# ZYNQ_SOC_FPGA.net
KiCad netlist of a schematic drawn in Altium Designer
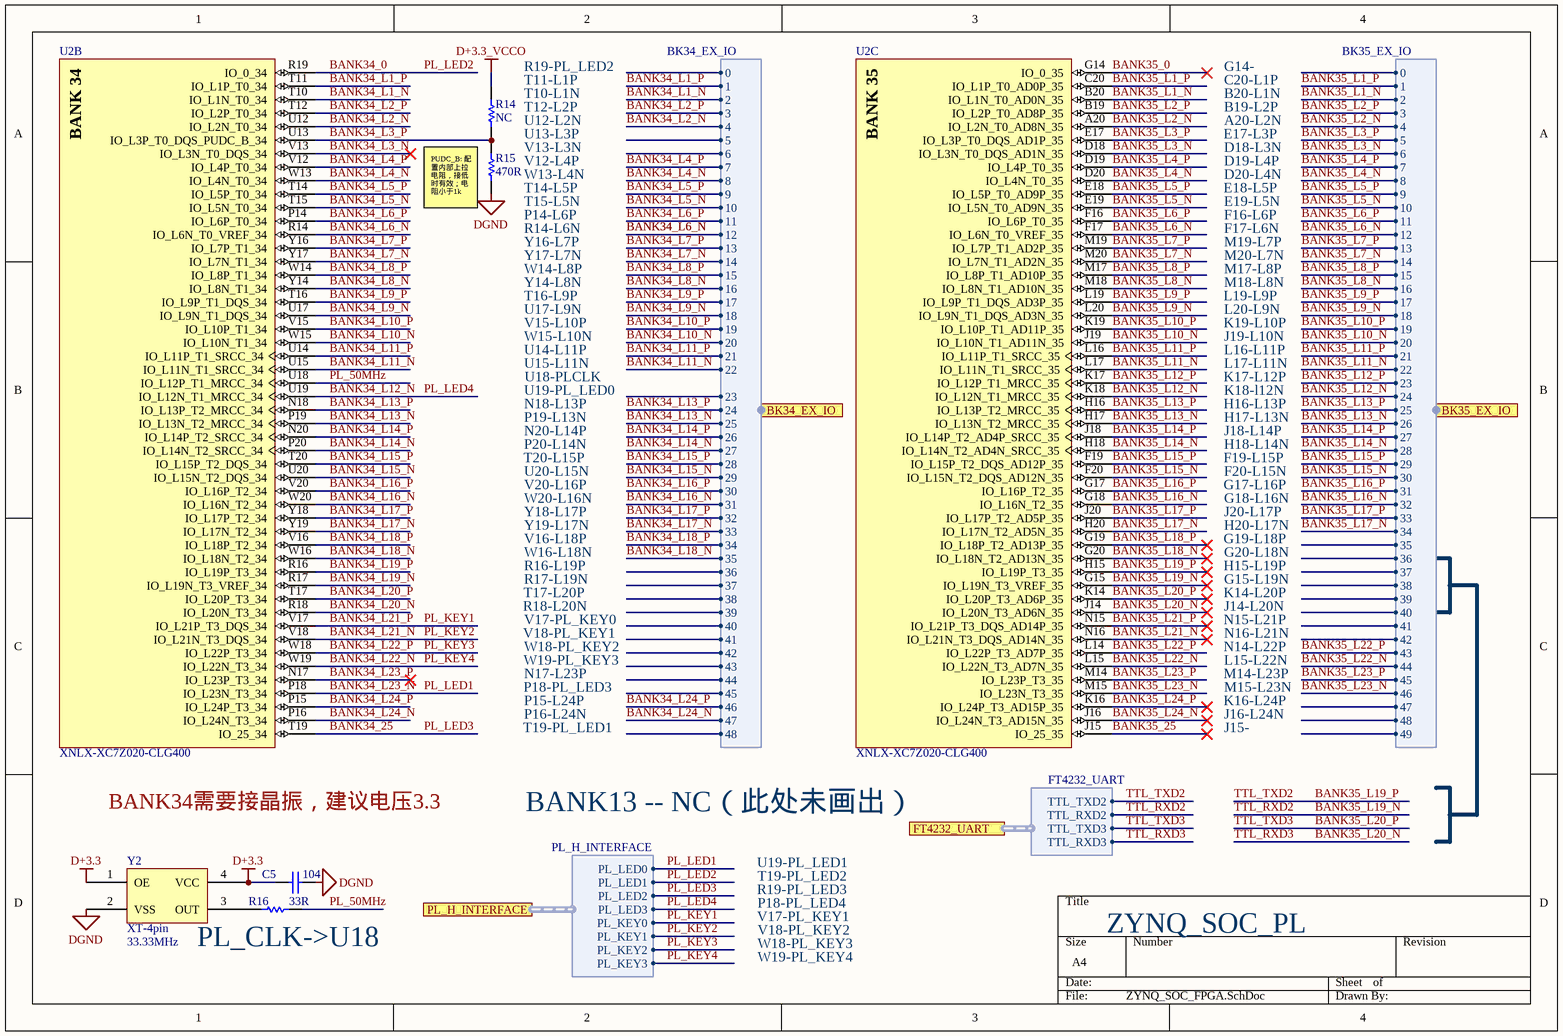
[diagram p0: ZYNQ_SOC_FPGA.SchDoc]

(export (version "E")
  (design (tool "Eeschema 10.0.6"))
  (components
    (comp (ref "C5")
      (value "104")
      (footprint "C 0402_LL")
      (description "Capacitor")
      (fields (field (name "PUBLISHER") "Altium Limited"))
      (libsource (lib "Miscellaneous Devices") (part "Cap"))
    )
    (comp (ref "R14")
      (value "NC")
      (footprint "R 0402_L")
      (description "Resistor")
      (fields (field (name "PUBLISHER") "Altium Limited"))
      (libsource (lib "Miscellaneous Devices") (part "Res1"))
    )
    (comp (ref "R15")
      (value "470R")
      (footprint "R 0402_L")
      (description "Resistor")
      (fields (field (name "PUBLISHER") "Altium Limited"))
      (libsource (lib "Miscellaneous Devices") (part "Res1"))
    )
    (comp (ref "R16")
      (value "33R")
      (footprint "R 0603_L")
      (description "Resistor")
      (fields (field (name "PUBLISHER") "Altium Limited"))
      (libsource (lib "Miscellaneous Devices") (part "Res1"))
    )
    (comp (ref "U2")
      (value "XNLX-XC7Z020-CLG400")
      (footprint "BGA400")
      (description "xilinx双核A9处理器与FPGA集成的SoC")
      (fields (field (name "MANUFACTURER") "xilinx"))
      (libsource (lib "龙井V1") (part "XNLX-XC7Z020-CLG400"))
    )
    (comp (ref "Y2")
      (value "XT-4pin")
      (footprint "5032(P)")
      (description "有源晶振")
      (fields (field (name "MANUFACTURER") "NC") (field (name "ALTIUM_VALUE") "33.33MHz"))
      (libsource (lib "龙井V1") (part "XT-4pin"))
    )
  )
  (nets
    (net (code "5") (name "/BANK34_0") (class "Default")
      (node (ref "U2") (pin "R19") (pinfunction "IO_0_34_R19") (pintype "bidirectional"))
    )
    (net (code "6") (name "/BANK34_25") (class "Default")
      (node (ref "U2") (pin "T19") (pinfunction "IO_25_34_T19") (pintype "bidirectional"))
    )
    (net (code "7") (name "/BANK34_L1_N") (class "Default")
      (node (ref "U2") (pin "T10") (pinfunction "IO_L1N_T0_34_T10") (pintype "bidirectional"))
    )
    (net (code "8") (name "/BANK34_L1_P") (class "Default")
      (node (ref "U2") (pin "T11") (pinfunction "IO_L1P_T0_34_T11") (pintype "bidirectional"))
    )
    (net (code "9") (name "/BANK34_L2_N") (class "Default")
      (node (ref "U2") (pin "U12") (pinfunction "IO_L2N_T0_34_U12") (pintype "bidirectional"))
    )
    (net (code "10") (name "/BANK34_L2_P") (class "Default")
      (node (ref "U2") (pin "T12") (pinfunction "IO_L2P_T0_34_T12") (pintype "bidirectional"))
    )
    (net (code "11") (name "/BANK34_L3_N") (class "Default")
      (node (ref "U2") (pin "V13") (pinfunction "IO_L3N_T0_DQS_34_V13") (pintype "bidirectional+no_connect"))
    )
    (net (code "12") (name "/BANK34_L3_P") (class "Default")
      (node (ref "R14") (pin "1") (pinfunction "1_1") (pintype "passive"))
      (node (ref "R15") (pin "2") (pinfunction "2_2") (pintype "passive"))
      (node (ref "U2") (pin "U13") (pinfunction "IO_L3P_T0_DQS_PUDC_B_34_U13") (pintype "bidirectional"))
    )
    (net (code "13") (name "/BANK34_L4_N") (class "Default")
      (node (ref "U2") (pin "W13") (pinfunction "IO_L4N_T0_34_W13") (pintype "bidirectional"))
    )
    (net (code "14") (name "/BANK34_L4_P") (class "Default")
      (node (ref "U2") (pin "V12") (pinfunction "IO_L4P_T0_34_V12") (pintype "bidirectional"))
    )
    (net (code "15") (name "/BANK34_L5_N") (class "Default")
      (node (ref "U2") (pin "T15") (pinfunction "IO_L5N_T0_34_T15") (pintype "bidirectional"))
    )
    (net (code "16") (name "/BANK34_L5_P") (class "Default")
      (node (ref "U2") (pin "T14") (pinfunction "IO_L5P_T0_34_T14") (pintype "bidirectional"))
    )
    (net (code "17") (name "/BANK34_L6_N") (class "Default")
      (node (ref "U2") (pin "R14") (pinfunction "IO_L6N_T0_VREF_34_R14") (pintype "bidirectional"))
    )
    (net (code "18") (name "/BANK34_L6_P") (class "Default")
      (node (ref "U2") (pin "P14") (pinfunction "IO_L6P_T0_34_P14") (pintype "bidirectional"))
    )
    (net (code "19") (name "/BANK34_L7_N") (class "Default")
      (node (ref "U2") (pin "Y17") (pinfunction "IO_L7N_T1_34_Y17") (pintype "bidirectional"))
    )
    (net (code "20") (name "/BANK34_L7_P") (class "Default")
      (node (ref "U2") (pin "Y16") (pinfunction "IO_L7P_T1_34_Y16") (pintype "bidirectional"))
    )
    (net (code "21") (name "/BANK34_L8_N") (class "Default")
      (node (ref "U2") (pin "Y14") (pinfunction "IO_L8N_T1_34_Y14") (pintype "bidirectional"))
    )
    (net (code "22") (name "/BANK34_L8_P") (class "Default")
      (node (ref "U2") (pin "W14") (pinfunction "IO_L8P_T1_34_W14") (pintype "bidirectional"))
    )
    (net (code "23") (name "/BANK34_L9_N") (class "Default")
      (node (ref "U2") (pin "U17") (pinfunction "IO_L9N_T1_DQS_34_U17") (pintype "bidirectional"))
    )
    (net (code "24") (name "/BANK34_L9_P") (class "Default")
      (node (ref "U2") (pin "T16") (pinfunction "IO_L9P_T1_DQS_34_T16") (pintype "bidirectional"))
    )
    (net (code "25") (name "/BANK34_L10_N") (class "Default")
      (node (ref "U2") (pin "W15") (pinfunction "IO_L10N_T1_34_W15") (pintype "bidirectional"))
    )
    (net (code "26") (name "/BANK34_L10_P") (class "Default")
      (node (ref "U2") (pin "V15") (pinfunction "IO_L10P_T1_34_V15") (pintype "bidirectional"))
    )
    (net (code "27") (name "/BANK34_L11_N") (class "Default")
      (node (ref "U2") (pin "U15") (pinfunction "IO_L11N_T1_SRCC_34_U15") (pintype "bidirectional"))
    )
    (net (code "28") (name "/BANK34_L11_P") (class "Default")
      (node (ref "U2") (pin "U14") (pinfunction "IO_L11P_T1_SRCC_34_U14") (pintype "bidirectional"))
    )
    (net (code "29") (name "/BANK34_L12_N") (class "Default")
      (node (ref "U2") (pin "U19") (pinfunction "IO_L12N_T1_MRCC_34_U19") (pintype "bidirectional"))
    )
    (net (code "30") (name "/BANK34_L13_N") (class "Default")
      (node (ref "U2") (pin "P19") (pinfunction "IO_L13N_T2_MRCC_34_P19") (pintype "bidirectional"))
    )
    (net (code "31") (name "/BANK34_L13_P") (class "Default")
      (node (ref "U2") (pin "N18") (pinfunction "IO_L13P_T2_MRCC_34_N18") (pintype "bidirectional"))
    )
    (net (code "32") (name "/BANK34_L14_N") (class "Default")
      (node (ref "U2") (pin "P20") (pinfunction "IO_L14N_T2_SRCC_34_P20") (pintype "bidirectional"))
    )
    (net (code "33") (name "/BANK34_L14_P") (class "Default")
      (node (ref "U2") (pin "N20") (pinfunction "IO_L14P_T2_SRCC_34_N20") (pintype "bidirectional"))
    )
    (net (code "34") (name "/BANK34_L15_N") (class "Default")
      (node (ref "U2") (pin "U20") (pinfunction "IO_L15N_T2_DQS_34_U20") (pintype "bidirectional"))
    )
    (net (code "35") (name "/BANK34_L15_P") (class "Default")
      (node (ref "U2") (pin "T20") (pinfunction "IO_L15P_T2_DQS_34_T20") (pintype "bidirectional"))
    )
    (net (code "36") (name "/BANK34_L16_N") (class "Default")
      (node (ref "U2") (pin "W20") (pinfunction "IO_L16N_T2_34_W20") (pintype "bidirectional"))
    )
    (net (code "37") (name "/BANK34_L16_P") (class "Default")
      (node (ref "U2") (pin "V20") (pinfunction "IO_L16P_T2_34_V20") (pintype "bidirectional"))
    )
    (net (code "38") (name "/BANK34_L17_N") (class "Default")
      (node (ref "U2") (pin "Y19") (pinfunction "IO_L17N_T2_34_Y19") (pintype "bidirectional"))
    )
    (net (code "39") (name "/BANK34_L17_P") (class "Default")
      (node (ref "U2") (pin "Y18") (pinfunction "IO_L17P_T2_34_Y18") (pintype "bidirectional"))
    )
    (net (code "40") (name "/BANK34_L18_N") (class "Default")
      (node (ref "U2") (pin "W16") (pinfunction "IO_L18N_T2_34_W16") (pintype "bidirectional"))
    )
    (net (code "41") (name "/BANK34_L18_P") (class "Default")
      (node (ref "U2") (pin "V16") (pinfunction "IO_L18P_T2_34_V16") (pintype "bidirectional"))
    )
    (net (code "42") (name "/BANK34_L19_N") (class "Default")
      (node (ref "U2") (pin "R17") (pinfunction "IO_L19N_T3_VREF_34_R17") (pintype "bidirectional"))
    )
    (net (code "43") (name "/BANK34_L19_P") (class "Default")
      (node (ref "U2") (pin "R16") (pinfunction "IO_L19P_T3_34_R16") (pintype "bidirectional"))
    )
    (net (code "44") (name "/BANK34_L20_N") (class "Default")
      (node (ref "U2") (pin "R18") (pinfunction "IO_L20N_T3_34_R18") (pintype "bidirectional"))
    )
    (net (code "45") (name "/BANK34_L20_P") (class "Default")
      (node (ref "U2") (pin "T17") (pinfunction "IO_L20P_T3_34_T17") (pintype "bidirectional"))
    )
    (net (code "46") (name "/BANK34_L21_N") (class "Default")
      (node (ref "U2") (pin "V18") (pinfunction "IO_L21N_T3_DQS_34_V18") (pintype "bidirectional"))
    )
    (net (code "47") (name "/BANK34_L21_P") (class "Default")
      (node (ref "U2") (pin "V17") (pinfunction "IO_L21P_T3_DQS_34_V17") (pintype "bidirectional"))
    )
    (net (code "48") (name "/BANK34_L22_N") (class "Default")
      (node (ref "U2") (pin "W19") (pinfunction "IO_L22N_T3_34_W19") (pintype "bidirectional"))
    )
    (net (code "49") (name "/BANK34_L22_P") (class "Default")
      (node (ref "U2") (pin "W18") (pinfunction "IO_L22P_T3_34_W18") (pintype "bidirectional"))
    )
    (net (code "50") (name "/BANK34_L23_N") (class "Default")
      (node (ref "U2") (pin "P18") (pinfunction "IO_L23N_T3_34_P18") (pintype "bidirectional"))
    )
    (net (code "51") (name "/BANK34_L23_P") (class "Default")
      (node (ref "U2") (pin "N17") (pinfunction "IO_L23P_T3_34_N17") (pintype "bidirectional+no_connect"))
    )
    (net (code "52") (name "/BANK34_L24_N") (class "Default")
      (node (ref "U2") (pin "P16") (pinfunction "IO_L24N_T3_34_P16") (pintype "bidirectional"))
    )
    (net (code "53") (name "/BANK34_L24_P") (class "Default")
      (node (ref "U2") (pin "P15") (pinfunction "IO_L24P_T3_34_P15") (pintype "bidirectional"))
    )
    (net (code "54") (name "/BANK35_0") (class "Default")
      (node (ref "U2") (pin "G14") (pinfunction "IO_0_35_G14") (pintype "bidirectional+no_connect"))
    )
    (net (code "55") (name "/BANK35_25") (class "Default")
      (node (ref "U2") (pin "J15") (pinfunction "IO_25_35_J15") (pintype "bidirectional+no_connect"))
    )
    (net (code "56") (name "/BANK35_L1_N") (class "Default")
      (node (ref "U2") (pin "B20") (pinfunction "IO_L1N_T0_AD0N_35_B20") (pintype "bidirectional"))
    )
    (net (code "57") (name "/BANK35_L1_P") (class "Default")
      (node (ref "U2") (pin "C20") (pinfunction "IO_L1P_T0_AD0P_35_C20") (pintype "bidirectional"))
    )
    (net (code "58") (name "/BANK35_L2_N") (class "Default")
      (node (ref "U2") (pin "A20") (pinfunction "IO_L2N_T0_AD8N_35_A20") (pintype "bidirectional"))
    )
    (net (code "59") (name "/BANK35_L2_P") (class "Default")
      (node (ref "U2") (pin "B19") (pinfunction "IO_L2P_T0_AD8P_35_B19") (pintype "bidirectional"))
    )
    (net (code "60") (name "/BANK35_L3_N") (class "Default")
      (node (ref "U2") (pin "D18") (pinfunction "IO_L3N_T0_DQS_AD1N_35_D18") (pintype "bidirectional"))
    )
    (net (code "61") (name "/BANK35_L3_P") (class "Default")
      (node (ref "U2") (pin "E17") (pinfunction "IO_L3P_T0_DQS_AD1P_35_E17") (pintype "bidirectional"))
    )
    (net (code "62") (name "/BANK35_L4_N") (class "Default")
      (node (ref "U2") (pin "D20") (pinfunction "IO_L4N_T0_35_D20") (pintype "bidirectional"))
    )
    (net (code "63") (name "/BANK35_L4_P") (class "Default")
      (node (ref "U2") (pin "D19") (pinfunction "IO_L4P_T0_35_D19") (pintype "bidirectional"))
    )
    (net (code "64") (name "/BANK35_L5_N") (class "Default")
      (node (ref "U2") (pin "E19") (pinfunction "IO_L5N_T0_AD9N_35_E19") (pintype "bidirectional"))
    )
    (net (code "65") (name "/BANK35_L5_P") (class "Default")
      (node (ref "U2") (pin "E18") (pinfunction "IO_L5P_T0_AD9P_35_E18") (pintype "bidirectional"))
    )
    (net (code "66") (name "/BANK35_L6_N") (class "Default")
      (node (ref "U2") (pin "F17") (pinfunction "IO_L6N_T0_VREF_35_F17") (pintype "bidirectional"))
    )
    (net (code "67") (name "/BANK35_L6_P") (class "Default")
      (node (ref "U2") (pin "F16") (pinfunction "IO_L6P_T0_35_F16") (pintype "bidirectional"))
    )
    (net (code "68") (name "/BANK35_L7_N") (class "Default")
      (node (ref "U2") (pin "M20") (pinfunction "IO_L7N_T1_AD2N_35_M20") (pintype "bidirectional"))
    )
    (net (code "69") (name "/BANK35_L7_P") (class "Default")
      (node (ref "U2") (pin "M19") (pinfunction "IO_L7P_T1_AD2P_35_M19") (pintype "bidirectional"))
    )
    (net (code "70") (name "/BANK35_L8_N") (class "Default")
      (node (ref "U2") (pin "M18") (pinfunction "IO_L8N_T1_AD10N_35_M18") (pintype "bidirectional"))
    )
    (net (code "71") (name "/BANK35_L8_P") (class "Default")
      (node (ref "U2") (pin "M17") (pinfunction "IO_L8P_T1_AD10P_35_M17") (pintype "bidirectional"))
    )
    (net (code "72") (name "/BANK35_L9_N") (class "Default")
      (node (ref "U2") (pin "L20") (pinfunction "IO_L9N_T1_DQS_AD3N_35_L20") (pintype "bidirectional"))
    )
    (net (code "73") (name "/BANK35_L9_P") (class "Default")
      (node (ref "U2") (pin "L19") (pinfunction "IO_L9P_T1_DQS_AD3P_35_L19") (pintype "bidirectional"))
    )
    (net (code "74") (name "/BANK35_L10_N") (class "Default")
      (node (ref "U2") (pin "J19") (pinfunction "IO_L10N_T1_AD11N_35_J19") (pintype "bidirectional"))
    )
    (net (code "75") (name "/BANK35_L10_P") (class "Default")
      (node (ref "U2") (pin "K19") (pinfunction "IO_L10P_T1_AD11P_35_K19") (pintype "bidirectional"))
    )
    (net (code "76") (name "/BANK35_L11_N") (class "Default")
      (node (ref "U2") (pin "L17") (pinfunction "IO_L11N_T1_SRCC_35_L17") (pintype "bidirectional"))
    )
    (net (code "77") (name "/BANK35_L11_P") (class "Default")
      (node (ref "U2") (pin "L16") (pinfunction "IO_L11P_T1_SRCC_35_L16") (pintype "bidirectional"))
    )
    (net (code "78") (name "/BANK35_L12_N") (class "Default")
      (node (ref "U2") (pin "K18") (pinfunction "IO_L12N_T1_MRCC_35_K18") (pintype "bidirectional"))
    )
    (net (code "79") (name "/BANK35_L12_P") (class "Default")
      (node (ref "U2") (pin "K17") (pinfunction "IO_L12P_T1_MRCC_35_K17") (pintype "bidirectional"))
    )
    (net (code "80") (name "/BANK35_L13_N") (class "Default")
      (node (ref "U2") (pin "H17") (pinfunction "IO_L13N_T2_MRCC_35_H17") (pintype "bidirectional"))
    )
    (net (code "81") (name "/BANK35_L13_P") (class "Default")
      (node (ref "U2") (pin "H16") (pinfunction "IO_L13P_T2_MRCC_35_H16") (pintype "bidirectional"))
    )
    (net (code "82") (name "/BANK35_L14_N") (class "Default")
      (node (ref "U2") (pin "H18") (pinfunction "IO_L14N_T2_AD4N_SRCC_35_H18") (pintype "bidirectional"))
    )
    (net (code "83") (name "/BANK35_L14_P") (class "Default")
      (node (ref "U2") (pin "J18") (pinfunction "IO_L14P_T2_AD4P_SRCC_35_J18") (pintype "bidirectional"))
    )
    (net (code "84") (name "/BANK35_L15_N") (class "Default")
      (node (ref "U2") (pin "F20") (pinfunction "IO_L15N_T2_DQS_AD12N_35_F20") (pintype "bidirectional"))
    )
    (net (code "85") (name "/BANK35_L15_P") (class "Default")
      (node (ref "U2") (pin "F19") (pinfunction "IO_L15P_T2_DQS_AD12P_35_F19") (pintype "bidirectional"))
    )
    (net (code "86") (name "/BANK35_L16_N") (class "Default")
      (node (ref "U2") (pin "G18") (pinfunction "IO_L16N_T2_35_G18") (pintype "bidirectional"))
    )
    (net (code "87") (name "/BANK35_L16_P") (class "Default")
      (node (ref "U2") (pin "G17") (pinfunction "IO_L16P_T2_35_G17") (pintype "bidirectional"))
    )
    (net (code "88") (name "/BANK35_L17_N") (class "Default")
      (node (ref "U2") (pin "H20") (pinfunction "IO_L17N_T2_AD5N_35_H20") (pintype "bidirectional"))
    )
    (net (code "89") (name "/BANK35_L17_P") (class "Default")
      (node (ref "U2") (pin "J20") (pinfunction "IO_L17P_T2_AD5P_35_J20") (pintype "bidirectional"))
    )
    (net (code "90") (name "/BANK35_L18_N") (class "Default")
      (node (ref "U2") (pin "G20") (pinfunction "IO_L18N_T2_AD13N_35_G20") (pintype "bidirectional+no_connect"))
    )
    (net (code "91") (name "/BANK35_L18_P") (class "Default")
      (node (ref "U2") (pin "G19") (pinfunction "IO_L18P_T2_AD13P_35_G19") (pintype "bidirectional+no_connect"))
    )
    (net (code "92") (name "/BANK35_L19_N") (class "Default")
      (node (ref "U2") (pin "G15") (pinfunction "IO_L19N_T3_VREF_35_G15") (pintype "bidirectional+no_connect"))
    )
    (net (code "93") (name "/BANK35_L19_P") (class "Default")
      (node (ref "U2") (pin "H15") (pinfunction "IO_L19P_T3_35_H15") (pintype "bidirectional+no_connect"))
    )
    (net (code "94") (name "/BANK35_L20_N") (class "Default")
      (node (ref "U2") (pin "J14") (pinfunction "IO_L20N_T3_AD6N_35_J14") (pintype "bidirectional+no_connect"))
    )
    (net (code "95") (name "/BANK35_L20_P") (class "Default")
      (node (ref "U2") (pin "K14") (pinfunction "IO_L20P_T3_AD6P_35_K14") (pintype "bidirectional+no_connect"))
    )
    (net (code "96") (name "/BANK35_L21_N") (class "Default")
      (node (ref "U2") (pin "N16") (pinfunction "IO_L21N_T3_DQS_AD14N_35_N16") (pintype "bidirectional+no_connect"))
    )
    (net (code "97") (name "/BANK35_L21_P") (class "Default")
      (node (ref "U2") (pin "N15") (pinfunction "IO_L21P_T3_DQS_AD14P_35_N15") (pintype "bidirectional+no_connect"))
    )
    (net (code "98") (name "/BANK35_L22_N") (class "Default")
      (node (ref "U2") (pin "L15") (pinfunction "IO_L22N_T3_AD7N_35_L15") (pintype "bidirectional"))
    )
    (net (code "99") (name "/BANK35_L22_P") (class "Default")
      (node (ref "U2") (pin "L14") (pinfunction "IO_L22P_T3_AD7P_35_L14") (pintype "bidirectional"))
    )
    (net (code "100") (name "/BANK35_L23_N") (class "Default")
      (node (ref "U2") (pin "M15") (pinfunction "IO_L23N_T3_35_M15") (pintype "bidirectional"))
    )
    (net (code "101") (name "/BANK35_L23_P") (class "Default")
      (node (ref "U2") (pin "M14") (pinfunction "IO_L23P_T3_35_M14") (pintype "bidirectional"))
    )
    (net (code "102") (name "/BANK35_L24_N") (class "Default")
      (node (ref "U2") (pin "J16") (pinfunction "IO_L24N_T3_AD15N_35_J16") (pintype "bidirectional+no_connect"))
    )
    (net (code "103") (name "/BANK35_L24_P") (class "Default")
      (node (ref "U2") (pin "K16") (pinfunction "IO_L24P_T3_AD15P_35_K16") (pintype "bidirectional+no_connect"))
    )
    (net (code "104") (name "/PL_50MHz") (class "Default")
      (node (ref "R16") (pin "2") (pinfunction "2_2") (pintype "passive"))
      (node (ref "U2") (pin "U18") (pinfunction "IO_L12P_T1_MRCC_34_U18") (pintype "bidirectional"))
    )
    (net (code "109") (name "D+3.3") (class "Default")
      (node (ref "C5") (pin "1") (pinfunction "1_1") (pintype "passive"))
      (node (ref "Y2") (pin "1") (pinfunction "OE_1") (pintype "passive"))
      (node (ref "Y2") (pin "4") (pinfunction "VCC_4") (pintype "passive"))
    )
    (net (code "110") (name "D+3.3_VCCO") (class "Default")
      (node (ref "R14") (pin "2") (pinfunction "2_2") (pintype "passive"))
    )
    (net (code "111") (name "DGND") (class "Default")
      (node (ref "C5") (pin "2") (pinfunction "2_2") (pintype "passive"))
      (node (ref "R15") (pin "1") (pinfunction "1_1") (pintype "passive"))
      (node (ref "Y2") (pin "2") (pinfunction "VSS_2") (pintype "passive"))
    )
    (net (code "112") (name "Net-(Y2-OUT)") (class "Default")
      (node (ref "R16") (pin "1") (pinfunction "1_1") (pintype "passive"))
      (node (ref "Y2") (pin "3") (pinfunction "OUT_3") (pintype "passive"))
    )
  )
)
